# design.net
KiCad netlist of a schematic drawn in Altium Designer
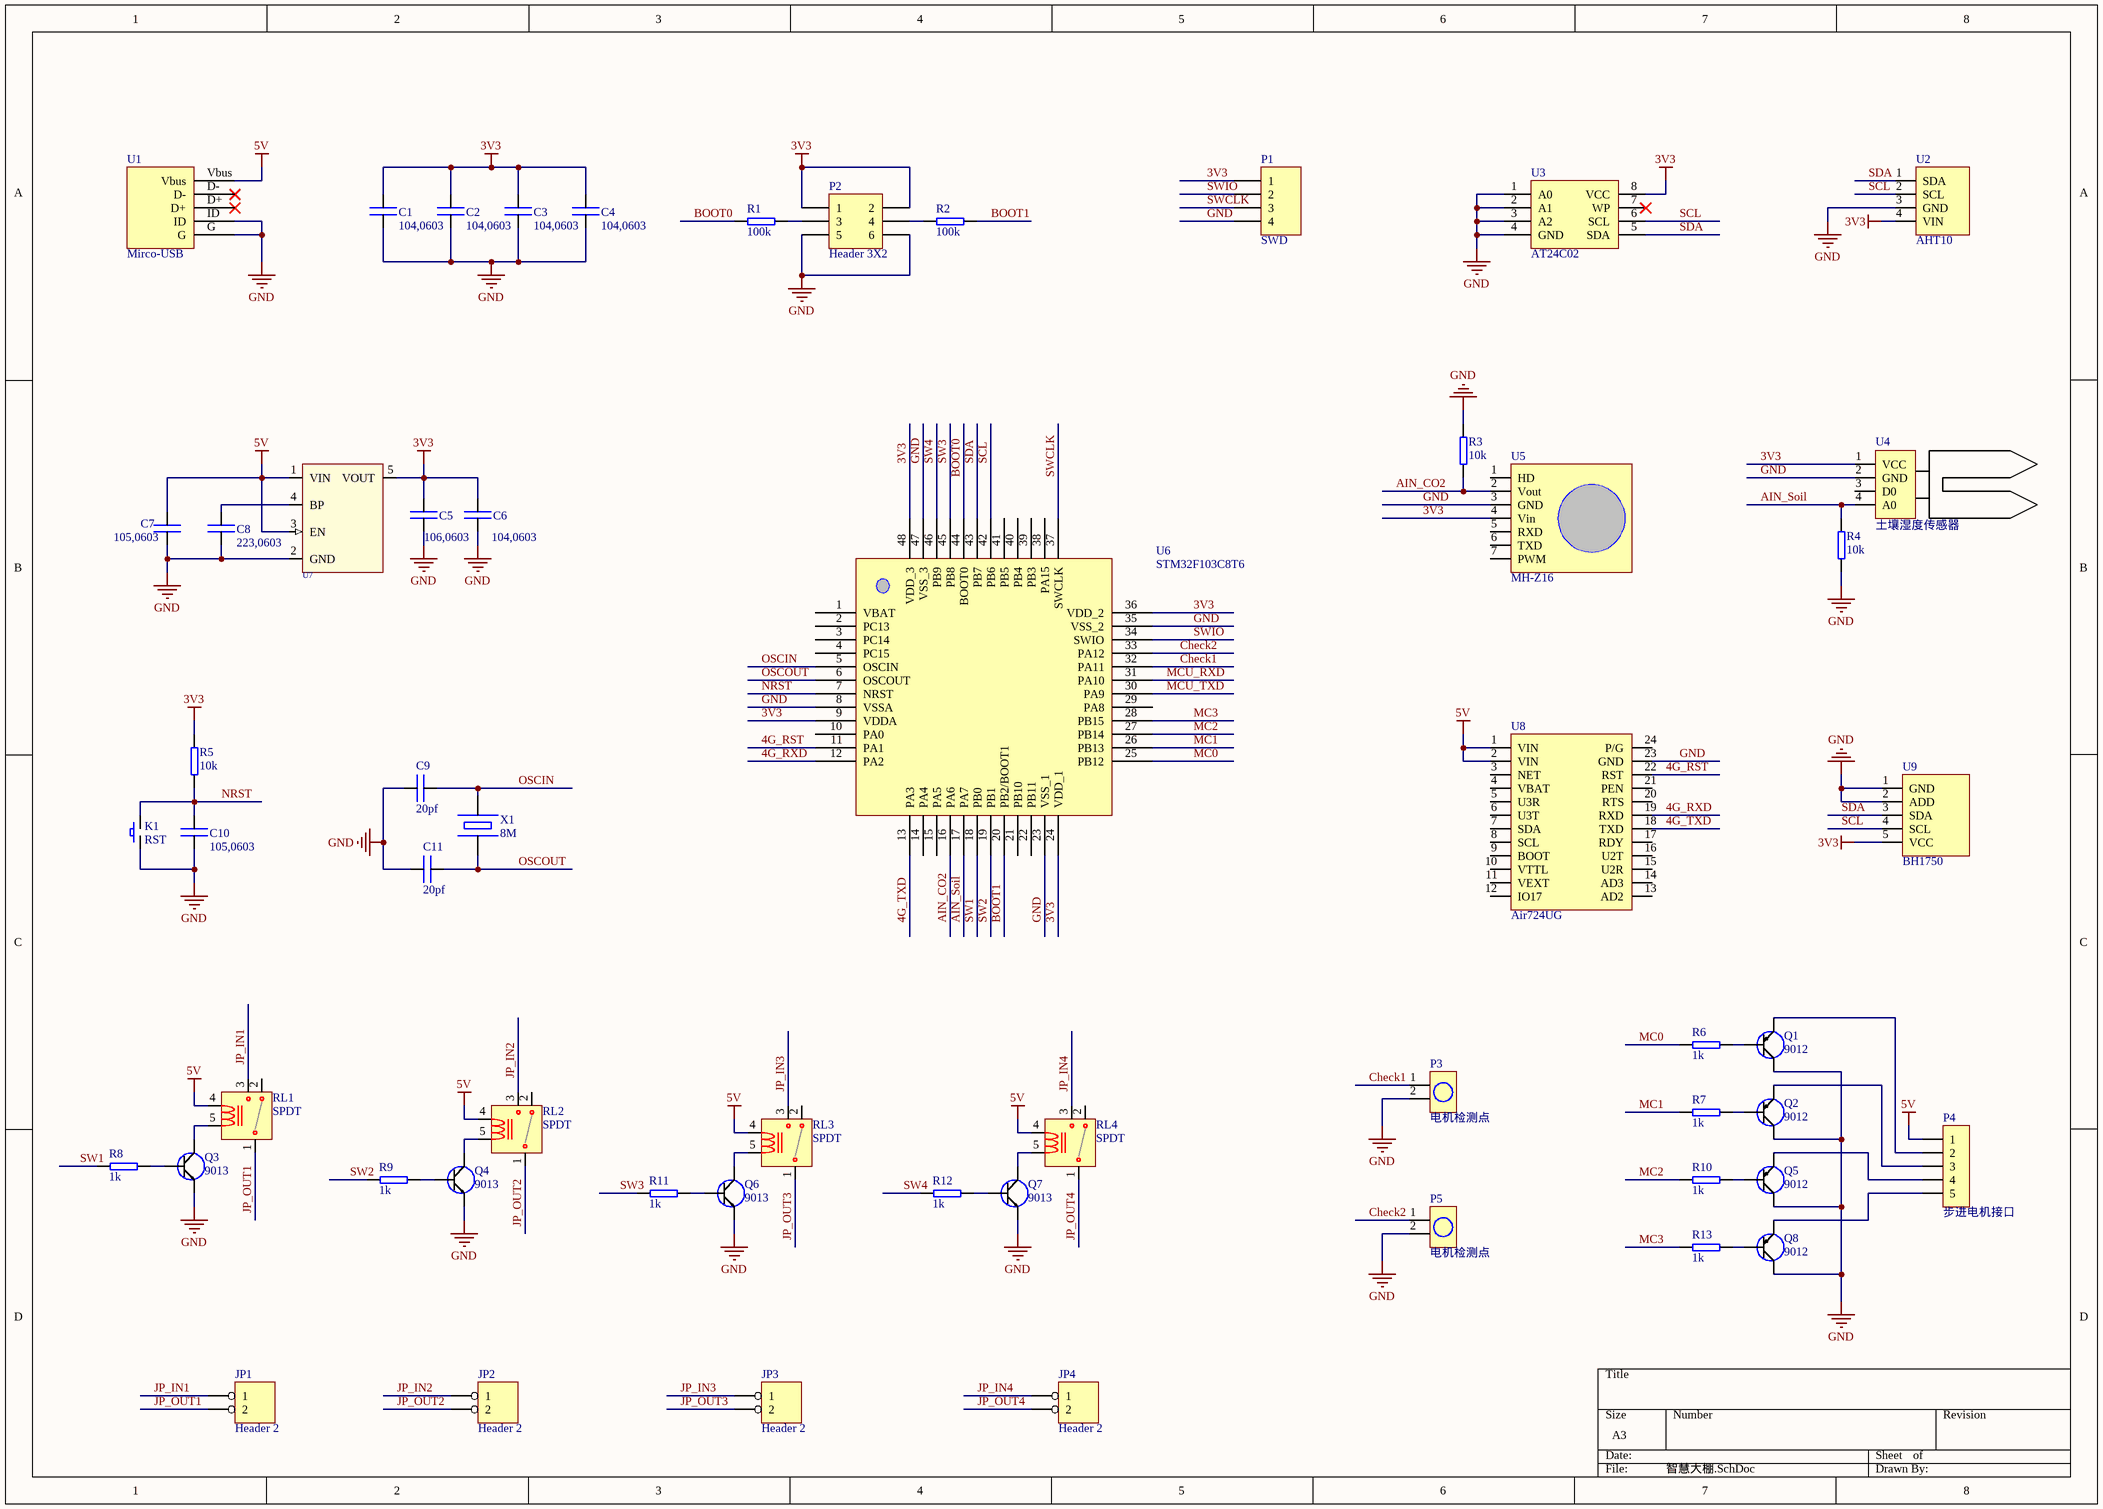
[diagram p0: 智慧大棚.SchDoc]

(export (version "E")
  (design (tool "Eeschema 10.0.6"))
  (components
    (comp (ref "C1")
      (value "104,0603")
      (description "电容")
      (libsource (lib "altium-import") (part "root_0_CAP_"))
    )
    (comp (ref "C2")
      (value "104,0603")
      (description "电容")
      (libsource (lib "altium-import") (part "root_0_CAP_"))
    )
    (comp (ref "C3")
      (value "104,0603")
      (description "电容")
      (libsource (lib "altium-import") (part "root_0_CAP_"))
    )
    (comp (ref "C4")
      (value "104,0603")
      (description "电容")
      (libsource (lib "altium-import") (part "root_0_CAP_"))
    )
    (comp (ref "C5") (value "106,0603") (description "电容") (libsource (lib "智慧大棚") (part "CAP")))
    (comp (ref "C6") (value "104,0603") (description "电容") (libsource (lib "智慧大棚") (part "CAP")))
    (comp (ref "C7")
      (value "105,0603")
      (description "电容")
      (libsource (lib "altium-import") (part "root_0_CAP_"))
    )
    (comp (ref "C8")
      (value "223,0603")
      (description "电容")
      (libsource (lib "altium-import") (part "root_0_CAP_"))
    )
    (comp (ref "C9") (value "20pf") (description "电容") (libsource (lib "altium-import") (part "root_1_CAP_")))
    (comp (ref "C10")
      (value "105,0603")
      (description "电容")
      (libsource (lib "altium-import") (part "root_0_CAP_"))
    )
    (comp (ref "C11")
      (value "20pf")
      (description "电容")
      (libsource (lib "altium-import") (part "root_1_CAP_"))
    )
    (comp (ref "JP1") (value "Header 2") (description "接线端子") (libsource (lib "智慧大棚") (part "Header 2")))
    (comp (ref "JP2") (value "Header 2") (description "接线端子") (libsource (lib "智慧大棚") (part "Header 2")))
    (comp (ref "JP3") (value "Header 2") (description "接线端子") (libsource (lib "智慧大棚") (part "Header 2")))
    (comp (ref "JP4") (value "Header 2") (description "接线端子") (libsource (lib "智慧大棚") (part "Header 2")))
    (comp (ref "K1")
      (value "RST")
      (description "微动开关")
      (libsource (lib "altium-import") (part "root_1_KEY_"))
    )
    (comp (ref "P1")
      (value "SWD")
      (footprint "HDR1X4")
      (description "Header, 4-Pin")
      (fields (field (name "PUBLISHER") "Altium Limited"))
      (libsource (lib "altium-import") (part "root_0_Header 4_"))
    )
    (comp (ref "P2")
      (value "Header 3X2")
      (footprint "HDR2X3")
      (description "Header, 3-Pin, Dual row")
      (fields (field (name "PUBLISHER") "Altium Limited"))
      (libsource (lib "altium-import") (part "root_0_Header 3X2_"))
    )
    (comp (ref "P3")
      (value "电机检测点")
      (description "电机位置检测点")
      (libsource (lib "altium-import") (part "root_0_Header 2IN_"))
    )
    (comp (ref "P4")
      (value "步进电机接口")
      (description "Header, 5-Pin")
      (libsource (lib "智慧大棚") (part "Header 5"))
    )
    (comp (ref "P5")
      (value "电机检测点")
      (description "电机位置检测点")
      (libsource (lib "altium-import") (part "root_0_Header 2IN_"))
    )
    (comp (ref "Q1")
      (value "9012")
      (description "PNP型三极管")
      (libsource (lib "altium-import") (part "root_0_PNP_"))
    )
    (comp (ref "Q2")
      (value "9012")
      (description "PNP型三极管")
      (libsource (lib "altium-import") (part "root_0_PNP_"))
    )
    (comp (ref "Q3") (value "9013") (libsource (lib "altium-import") (part "root_0_9013_")))
    (comp (ref "Q4") (value "9013") (libsource (lib "altium-import") (part "root_0_9013_")))
    (comp (ref "Q5")
      (value "9012")
      (description "PNP型三极管")
      (libsource (lib "altium-import") (part "root_0_PNP_"))
    )
    (comp (ref "Q6") (value "9013") (libsource (lib "altium-import") (part "root_0_9013_")))
    (comp (ref "Q7") (value "9013") (libsource (lib "altium-import") (part "root_0_9013_")))
    (comp (ref "Q8")
      (value "9012")
      (description "PNP型三极管")
      (libsource (lib "altium-import") (part "root_0_PNP_"))
    )
    (comp (ref "R1") (value "100k") (description "电阻") (libsource (lib "智慧大棚") (part "RES")))
    (comp (ref "R2") (value "100k") (description "电阻") (libsource (lib "智慧大棚") (part "RES")))
    (comp (ref "R3") (value "10k") (description "电阻") (libsource (lib "altium-import") (part "root_1_RES_")))
    (comp (ref "R4") (value "10k") (description "电阻") (libsource (lib "altium-import") (part "root_1_RES_")))
    (comp (ref "R5") (value "10k") (description "电阻") (libsource (lib "altium-import") (part "root_1_RES_")))
    (comp (ref "R6") (value "1k") (description "电阻") (libsource (lib "altium-import") (part "root_0_RES_")))
    (comp (ref "R7") (value "1k") (description "电阻") (libsource (lib "altium-import") (part "root_0_RES_")))
    (comp (ref "R8") (value "1k") (description "电阻") (libsource (lib "altium-import") (part "root_0_RES_")))
    (comp (ref "R9") (value "1k") (description "电阻") (libsource (lib "altium-import") (part "root_0_RES_")))
    (comp (ref "R10") (value "1k") (description "电阻") (libsource (lib "altium-import") (part "root_0_RES_")))
    (comp (ref "R11") (value "1k") (description "电阻") (libsource (lib "altium-import") (part "root_0_RES_")))
    (comp (ref "R12") (value "1k") (description "电阻") (libsource (lib "altium-import") (part "root_0_RES_")))
    (comp (ref "R13") (value "1k") (description "电阻") (libsource (lib "altium-import") (part "root_0_RES_")))
    (comp (ref "RL1") (value "SPDT") (libsource (lib "altium-import") (part "root_0_SPDT_")))
    (comp (ref "RL2") (value "SPDT") (libsource (lib "altium-import") (part "root_0_SPDT_")))
    (comp (ref "RL3") (value "SPDT") (libsource (lib "altium-import") (part "root_0_SPDT_")))
    (comp (ref "RL4") (value "SPDT") (libsource (lib "altium-import") (part "root_0_SPDT_")))
    (comp (ref "U1")
      (value "Mirco-USB")
      (footprint "Micro_USB")
      (description "Mirco-USB接口")
      (libsource (lib "altium-import") (part "root_0_Mirco-USB_"))
    )
    (comp (ref "U2")
      (value "AHT10")
      (description "温湿度传感器")
      (libsource (lib "altium-import") (part "root_0_AHT10_"))
    )
    (comp (ref "U3")
      (value "AT24C02")
      (description "EEPROM器件")
      (libsource (lib "altium-import") (part "root_0_AT24C02_"))
    )
    (comp (ref "U4") (value "土壤湿度传感器") (libsource (lib "altium-import") (part "root_0_Soil_")))
    (comp (ref "U5") (value "MH-Z16") (description "二氧化碳传感器") (libsource (lib "智慧大棚") (part "MH-Z16")))
    (comp (ref "U6")
      (value "STM32F103C8T6")
      (footprint "48P")
      (description "MCU 32bit")
      (libsource (lib "altium-import") (part "root_0_STM32F103C8T6_"))
    )
    (comp (ref "U7")
      (value "RT9193")
      (description "稳压")
      (fields (field (name "ICA_PARTNUM") "$$2191094$$RT9193-15CU5") (field (name "PART NUMBER") "TMP-13"))
      (libsource (lib "altium-import") (part "root_0_RT9193X_5P_"))
    )
    (comp (ref "U8")
      (value "Air724UG")
      (description "4G模块")
      (libsource (lib "altium-import") (part "root_0_Air724UG_"))
    )
    (comp (ref "U9")
      (value "BH1750")
      (description "光照传感器")
      (libsource (lib "altium-import") (part "root_0_BH1750_"))
    )
    (comp (ref "X1")
      (value "8M")
      (description "晶振")
      (libsource (lib "altium-import") (part "root_1_CRYSTAL_"))
    )
  )
  (nets
    (net (code "1") (name "/4G_RST") (class "Default")
      (node (ref "U6") (pin "11") (pinfunction "PA1_11") (pintype "passive"))
      (node (ref "U8") (pin "22") (pinfunction "RST_22") (pintype "passive"))
    )
    (net (code "2") (name "/4G_RXD") (class "Default")
      (node (ref "U6") (pin "12") (pinfunction "PA2_12") (pintype "passive"))
      (node (ref "U8") (pin "19") (pinfunction "RXD_19") (pintype "passive"))
    )
    (net (code "3") (name "/4G_TXD") (class "Default")
      (node (ref "U6") (pin "13") (pinfunction "PA3_13") (pintype "passive"))
      (node (ref "U8") (pin "18") (pinfunction "TXD_18") (pintype "passive"))
    )
    (net (code "4") (name "/AIN_CO2") (class "Default")
      (node (ref "R3") (pin "1") (pinfunction "1_1") (pintype "passive"))
      (node (ref "U5") (pin "2") (pinfunction "Vout_2") (pintype "passive"))
      (node (ref "U6") (pin "16") (pinfunction "PA6_16") (pintype "passive"))
    )
    (net (code "5") (name "/AIN_Soil") (class "Default")
      (node (ref "R4") (pin "2") (pinfunction "2_2") (pintype "passive"))
      (node (ref "U4") (pin "4") (pinfunction "A0_4") (pintype "passive"))
      (node (ref "U6") (pin "17") (pinfunction "PA7_17") (pintype "passive"))
    )
    (net (code "6") (name "/BOOT0") (class "Default")
      (node (ref "R1") (pin "1") (pinfunction "1_1") (pintype "passive"))
      (node (ref "U6") (pin "44") (pinfunction "BOOT0_44") (pintype "passive"))
    )
    (net (code "7") (name "/BOOT1") (class "Default")
      (node (ref "R2") (pin "2") (pinfunction "2_2") (pintype "passive"))
      (node (ref "U6") (pin "20") (pinfunction "PB2/BOOT1_20") (pintype "passive"))
    )
    (net (code "8") (name "/Check1") (class "Default")
      (node (ref "P3") (pin "1") (pinfunction "1_1") (pintype "passive"))
      (node (ref "U6") (pin "32") (pinfunction "PA11_32") (pintype "passive"))
    )
    (net (code "9") (name "/Check2") (class "Default")
      (node (ref "P5") (pin "1") (pinfunction "1_1") (pintype "passive"))
      (node (ref "U6") (pin "33") (pinfunction "PA12_33") (pintype "passive"))
    )
    (net (code "10") (name "/JP_IN1") (class "Default")
      (node (ref "JP1") (pin "1") (pinfunction "1_1") (pintype "passive"))
      (node (ref "RL1") (pin "3") (pinfunction "3_3") (pintype "passive"))
    )
    (net (code "11") (name "/JP_IN2") (class "Default")
      (node (ref "JP2") (pin "1") (pinfunction "1_1") (pintype "passive"))
      (node (ref "RL2") (pin "3") (pinfunction "3_3") (pintype "passive"))
    )
    (net (code "12") (name "/JP_IN3") (class "Default")
      (node (ref "JP3") (pin "1") (pinfunction "1_1") (pintype "passive"))
      (node (ref "RL3") (pin "3") (pinfunction "3_3") (pintype "passive"))
    )
    (net (code "13") (name "/JP_IN4") (class "Default")
      (node (ref "JP4") (pin "1") (pinfunction "1_1") (pintype "passive"))
      (node (ref "RL4") (pin "3") (pinfunction "3_3") (pintype "passive"))
    )
    (net (code "14") (name "/JP_OUT1") (class "Default")
      (node (ref "JP1") (pin "2") (pinfunction "2_2") (pintype "passive"))
      (node (ref "RL1") (pin "1") (pinfunction "1_1") (pintype "passive"))
    )
    (net (code "15") (name "/JP_OUT2") (class "Default")
      (node (ref "JP2") (pin "2") (pinfunction "2_2") (pintype "passive"))
      (node (ref "RL2") (pin "1") (pinfunction "1_1") (pintype "passive"))
    )
    (net (code "16") (name "/JP_OUT3") (class "Default")
      (node (ref "JP3") (pin "2") (pinfunction "2_2") (pintype "passive"))
      (node (ref "RL3") (pin "1") (pinfunction "1_1") (pintype "passive"))
    )
    (net (code "17") (name "/JP_OUT4") (class "Default")
      (node (ref "JP4") (pin "2") (pinfunction "2_2") (pintype "passive"))
      (node (ref "RL4") (pin "1") (pinfunction "1_1") (pintype "passive"))
    )
    (net (code "18") (name "/MC0") (class "Default")
      (node (ref "R6") (pin "1") (pinfunction "1_1") (pintype "passive"))
      (node (ref "U6") (pin "25") (pinfunction "PB12_25") (pintype "passive"))
    )
    (net (code "19") (name "/MC1") (class "Default")
      (node (ref "R7") (pin "1") (pinfunction "1_1") (pintype "passive"))
      (node (ref "U6") (pin "26") (pinfunction "PB13_26") (pintype "passive"))
    )
    (net (code "20") (name "/MC2") (class "Default")
      (node (ref "R10") (pin "1") (pinfunction "1_1") (pintype "passive"))
      (node (ref "U6") (pin "27") (pinfunction "PB14_27") (pintype "passive"))
    )
    (net (code "21") (name "/MC3") (class "Default")
      (node (ref "R13") (pin "1") (pinfunction "1_1") (pintype "passive"))
      (node (ref "U6") (pin "28") (pinfunction "PB15_28") (pintype "passive"))
    )
    (net (code "22") (name "/MCU_RXD") (class "Default")
      (node (ref "U6") (pin "31") (pinfunction "PA10_31") (pintype "passive"))
    )
    (net (code "23") (name "/MCU_TXD") (class "Default")
      (node (ref "U6") (pin "30") (pinfunction "PA9_30") (pintype "passive"))
    )
    (net (code "24") (name "/NRST") (class "Default")
      (node (ref "C10") (pin "1") (pinfunction "1_1") (pintype "passive"))
      (node (ref "K1") (pin "2") (pintype "passive"))
      (node (ref "R5") (pin "1") (pinfunction "1_1") (pintype "passive"))
      (node (ref "U6") (pin "7") (pinfunction "NRST_7") (pintype "passive"))
    )
    (net (code "25") (name "/OSCIN") (class "Default")
      (node (ref "C9") (pin "2") (pinfunction "2_2") (pintype "passive"))
      (node (ref "U6") (pin "5") (pinfunction "OSCIN_5") (pintype "passive"))
      (node (ref "X1") (pin "2") (pinfunction "2_2") (pintype "passive"))
    )
    (net (code "26") (name "/OSCOUT") (class "Default")
      (node (ref "C11") (pin "2") (pinfunction "2_2") (pintype "passive"))
      (node (ref "U6") (pin "6") (pinfunction "OSCOUT_6") (pintype "passive"))
      (node (ref "X1") (pin "1") (pinfunction "1_1") (pintype "passive"))
    )
    (net (code "27") (name "/SCL") (class "Default")
      (node (ref "U2") (pin "2") (pinfunction "SCL_2") (pintype "passive"))
      (node (ref "U3") (pin "6") (pinfunction "SCL_6") (pintype "passive"))
      (node (ref "U6") (pin "42") (pinfunction "PB6_42") (pintype "passive"))
      (node (ref "U9") (pin "4") (pinfunction "SCL_4") (pintype "passive"))
    )
    (net (code "28") (name "/SDA") (class "Default")
      (node (ref "U2") (pin "1") (pinfunction "SDA_1") (pintype "passive"))
      (node (ref "U3") (pin "5") (pinfunction "SDA_5") (pintype "passive"))
      (node (ref "U6") (pin "43") (pinfunction "PB7_43") (pintype "passive"))
      (node (ref "U9") (pin "3") (pinfunction "SDA_3") (pintype "passive"))
    )
    (net (code "29") (name "/SW1") (class "Default")
      (node (ref "R8") (pin "1") (pinfunction "1_1") (pintype "passive"))
      (node (ref "U6") (pin "18") (pinfunction "PB0_18") (pintype "passive"))
    )
    (net (code "30") (name "/SW2") (class "Default")
      (node (ref "R9") (pin "1") (pinfunction "1_1") (pintype "passive"))
      (node (ref "U6") (pin "19") (pinfunction "PB1_19") (pintype "passive"))
    )
    (net (code "31") (name "/SW3") (class "Default")
      (node (ref "R11") (pin "1") (pinfunction "1_1") (pintype "passive"))
      (node (ref "U6") (pin "45") (pinfunction "PB8_45") (pintype "passive"))
    )
    (net (code "32") (name "/SW4") (class "Default")
      (node (ref "R12") (pin "1") (pinfunction "1_1") (pintype "passive"))
      (node (ref "U6") (pin "46") (pinfunction "PB9_46") (pintype "passive"))
    )
    (net (code "33") (name "/SWCLK") (class "Default")
      (node (ref "P1") (pin "3") (pinfunction "3_3") (pintype "passive"))
      (node (ref "U6") (pin "37") (pinfunction "SWCLK_37") (pintype "passive"))
    )
    (net (code "34") (name "/SWIO") (class "Default")
      (node (ref "P1") (pin "2") (pinfunction "2_2") (pintype "passive"))
      (node (ref "U6") (pin "34") (pinfunction "SWIO_34") (pintype "passive"))
    )
    (net (code "35") (name "3V3") (class "Default")
      (node (ref "C1") (pin "1") (pinfunction "1_1") (pintype "passive"))
      (node (ref "C2") (pin "1") (pinfunction "1_1") (pintype "passive"))
      (node (ref "C3") (pin "1") (pinfunction "1_1") (pintype "passive"))
      (node (ref "C4") (pin "1") (pinfunction "1_1") (pintype "passive"))
      (node (ref "C5") (pin "1") (pinfunction "1_1") (pintype "passive"))
      (node (ref "C6") (pin "1") (pinfunction "1_1") (pintype "passive"))
      (node (ref "P1") (pin "1") (pinfunction "1_1") (pintype "passive"))
      (node (ref "P2") (pin "1") (pinfunction "1_1") (pintype "passive"))
      (node (ref "P2") (pin "2") (pinfunction "2_2") (pintype "passive"))
      (node (ref "R5") (pin "2") (pinfunction "2_2") (pintype "passive"))
      (node (ref "U2") (pin "4") (pinfunction "VIN_4") (pintype "passive"))
      (node (ref "U3") (pin "8") (pinfunction "VCC_8") (pintype "passive"))
      (node (ref "U4") (pin "1") (pinfunction "VCC_1") (pintype "passive"))
      (node (ref "U5") (pin "4") (pinfunction "Vin_4") (pintype "passive"))
      (node (ref "U6") (pin "24") (pinfunction "VDD_1_24") (pintype "passive"))
      (node (ref "U6") (pin "36") (pinfunction "VDD_2_36") (pintype "passive"))
      (node (ref "U6") (pin "48") (pinfunction "VDD_3_48") (pintype "passive"))
      (node (ref "U6") (pin "9") (pinfunction "VDDA_9") (pintype "passive"))
      (node (ref "U7") (pin "5") (pinfunction "VOUT_5") (pintype "power_in"))
      (node (ref "U9") (pin "5") (pinfunction "VCC_5") (pintype "passive"))
    )
    (net (code "36") (name "5V") (class "Default")
      (node (ref "C7") (pin "1") (pinfunction "1_1") (pintype "passive"))
      (node (ref "P4") (pin "1") (pinfunction "1_1") (pintype "passive"))
      (node (ref "RL1") (pin "4") (pinfunction "4_4") (pintype "passive"))
      (node (ref "RL2") (pin "4") (pinfunction "4_4") (pintype "passive"))
      (node (ref "RL3") (pin "4") (pinfunction "4_4") (pintype "passive"))
      (node (ref "RL4") (pin "4") (pinfunction "4_4") (pintype "passive"))
      (node (ref "U1") (pin "Vbus") (pinfunction "Vbus_Vbus") (pintype "passive"))
      (node (ref "U7") (pin "1") (pinfunction "VIN_1") (pintype "power_in"))
      (node (ref "U7") (pin "3") (pinfunction "EN_3") (pintype "input"))
      (node (ref "U8") (pin "1") (pinfunction "VIN_1") (pintype "passive"))
      (node (ref "U8") (pin "2") (pinfunction "VIN_2") (pintype "passive"))
    )
    (net (code "37") (name "GND") (class "Default")
      (node (ref "C1") (pin "2") (pinfunction "2_2") (pintype "passive"))
      (node (ref "C10") (pin "2") (pinfunction "2_2") (pintype "passive"))
      (node (ref "C11") (pin "1") (pinfunction "1_1") (pintype "passive"))
      (node (ref "C2") (pin "2") (pinfunction "2_2") (pintype "passive"))
      (node (ref "C3") (pin "2") (pinfunction "2_2") (pintype "passive"))
      (node (ref "C4") (pin "2") (pinfunction "2_2") (pintype "passive"))
      (node (ref "C5") (pin "2") (pinfunction "2_2") (pintype "passive"))
      (node (ref "C6") (pin "2") (pinfunction "2_2") (pintype "passive"))
      (node (ref "C7") (pin "2") (pinfunction "2_2") (pintype "passive"))
      (node (ref "C8") (pin "2") (pinfunction "2_2") (pintype "passive"))
      (node (ref "C9") (pin "1") (pinfunction "1_1") (pintype "passive"))
      (node (ref "K1") (pin "1") (pintype "passive"))
      (node (ref "P1") (pin "4") (pinfunction "4_4") (pintype "passive"))
      (node (ref "P2") (pin "5") (pinfunction "5_5") (pintype "passive"))
      (node (ref "P2") (pin "6") (pinfunction "6_6") (pintype "passive"))
      (node (ref "P3") (pin "2") (pinfunction "2_2") (pintype "passive"))
      (node (ref "P5") (pin "2") (pinfunction "2_2") (pintype "passive"))
      (node (ref "Q1") (pin "2") (pinfunction "2_2") (pintype "passive"))
      (node (ref "Q2") (pin "2") (pinfunction "2_2") (pintype "passive"))
      (node (ref "Q3") (pin "2") (pinfunction "2_2") (pintype "passive"))
      (node (ref "Q4") (pin "2") (pinfunction "2_2") (pintype "passive"))
      (node (ref "Q5") (pin "2") (pinfunction "2_2") (pintype "passive"))
      (node (ref "Q6") (pin "2") (pinfunction "2_2") (pintype "passive"))
      (node (ref "Q7") (pin "2") (pinfunction "2_2") (pintype "passive"))
      (node (ref "Q8") (pin "2") (pinfunction "2_2") (pintype "passive"))
      (node (ref "R3") (pin "2") (pinfunction "2_2") (pintype "passive"))
      (node (ref "R4") (pin "1") (pinfunction "1_1") (pintype "passive"))
      (node (ref "U1") (pin "G") (pinfunction "G_G") (pintype "passive"))
      (node (ref "U1") (pin "ID") (pinfunction "ID_ID") (pintype "passive"))
      (node (ref "U2") (pin "3") (pinfunction "GND_3") (pintype "passive"))
      (node (ref "U3") (pin "1") (pinfunction "A0_1") (pintype "passive"))
      (node (ref "U3") (pin "2") (pinfunction "A1_2") (pintype "passive"))
      (node (ref "U3") (pin "3") (pinfunction "A2_3") (pintype "passive"))
      (node (ref "U3") (pin "4") (pinfunction "GND_4") (pintype "passive"))
      (node (ref "U4") (pin "2") (pinfunction "GND_2") (pintype "passive"))
      (node (ref "U5") (pin "3") (pinfunction "GND_3") (pintype "passive"))
      (node (ref "U6") (pin "23") (pinfunction "VSS_1_23") (pintype "passive"))
      (node (ref "U6") (pin "35") (pinfunction "VSS_2_35") (pintype "passive"))
      (node (ref "U6") (pin "47") (pinfunction "VSS_3_47") (pintype "passive"))
      (node (ref "U6") (pin "8") (pinfunction "VSSA_8") (pintype "passive"))
      (node (ref "U7") (pin "2") (pinfunction "GND_2") (pintype "power_in"))
      (node (ref "U8") (pin "23") (pinfunction "GND_23") (pintype "passive"))
      (node (ref "U9") (pin "1") (pinfunction "GND_1") (pintype "passive"))
      (node (ref "U9") (pin "2") (pinfunction "ADD_2") (pintype "passive"))
    )
    (net (code "38") (name "Net-(P2-Pad3)") (class "Default")
      (node (ref "P2") (pin "3") (pinfunction "3_3") (pintype "passive"))
      (node (ref "R1") (pin "2") (pinfunction "2_2") (pintype "passive"))
    )
    (net (code "39") (name "Net-(P2-Pad4)") (class "Default")
      (node (ref "P2") (pin "4") (pinfunction "4_4") (pintype "passive"))
      (node (ref "R2") (pin "1") (pinfunction "1_1") (pintype "passive"))
    )
    (net (code "40") (name "Net-(P4-Pad2)") (class "Default")
      (node (ref "P4") (pin "2") (pinfunction "2_2") (pintype "passive"))
      (node (ref "Q1") (pin "3") (pinfunction "3_3") (pintype "passive"))
    )
    (net (code "41") (name "Net-(P4-Pad3)") (class "Default")
      (node (ref "P4") (pin "3") (pinfunction "3_3") (pintype "passive"))
      (node (ref "Q2") (pin "3") (pinfunction "3_3") (pintype "passive"))
    )
    (net (code "42") (name "Net-(P4-Pad4)") (class "Default")
      (node (ref "P4") (pin "4") (pinfunction "4_4") (pintype "passive"))
      (node (ref "Q5") (pin "3") (pinfunction "3_3") (pintype "passive"))
    )
    (net (code "43") (name "Net-(P4-Pad5)") (class "Default")
      (node (ref "P4") (pin "5") (pinfunction "5_5") (pintype "passive"))
      (node (ref "Q8") (pin "3") (pinfunction "3_3") (pintype "passive"))
    )
    (net (code "44") (name "Net-(Q1-Pad1)") (class "Default")
      (node (ref "Q1") (pin "1") (pinfunction "1_1") (pintype "passive"))
      (node (ref "R6") (pin "2") (pinfunction "2_2") (pintype "passive"))
    )
    (net (code "45") (name "Net-(Q2-Pad1)") (class "Default")
      (node (ref "Q2") (pin "1") (pinfunction "1_1") (pintype "passive"))
      (node (ref "R7") (pin "2") (pinfunction "2_2") (pintype "passive"))
    )
    (net (code "46") (name "Net-(Q3-Pad1)") (class "Default")
      (node (ref "Q3") (pin "1") (pinfunction "1_1") (pintype "passive"))
      (node (ref "R8") (pin "2") (pinfunction "2_2") (pintype "passive"))
    )
    (net (code "47") (name "Net-(Q3-Pad3)") (class "Default")
      (node (ref "Q3") (pin "3") (pinfunction "3_3") (pintype "passive"))
      (node (ref "RL1") (pin "5") (pinfunction "5_5") (pintype "passive"))
    )
    (net (code "48") (name "Net-(Q4-Pad1)") (class "Default")
      (node (ref "Q4") (pin "1") (pinfunction "1_1") (pintype "passive"))
      (node (ref "R9") (pin "2") (pinfunction "2_2") (pintype "passive"))
    )
    (net (code "49") (name "Net-(Q4-Pad3)") (class "Default")
      (node (ref "Q4") (pin "3") (pinfunction "3_3") (pintype "passive"))
      (node (ref "RL2") (pin "5") (pinfunction "5_5") (pintype "passive"))
    )
    (net (code "50") (name "Net-(Q5-Pad1)") (class "Default")
      (node (ref "Q5") (pin "1") (pinfunction "1_1") (pintype "passive"))
      (node (ref "R10") (pin "2") (pinfunction "2_2") (pintype "passive"))
    )
    (net (code "51") (name "Net-(Q6-Pad1)") (class "Default")
      (node (ref "Q6") (pin "1") (pinfunction "1_1") (pintype "passive"))
      (node (ref "R11") (pin "2") (pinfunction "2_2") (pintype "passive"))
    )
    (net (code "52") (name "Net-(Q6-Pad3)") (class "Default")
      (node (ref "Q6") (pin "3") (pinfunction "3_3") (pintype "passive"))
      (node (ref "RL3") (pin "5") (pinfunction "5_5") (pintype "passive"))
    )
    (net (code "53") (name "Net-(Q7-Pad1)") (class "Default")
      (node (ref "Q7") (pin "1") (pinfunction "1_1") (pintype "passive"))
      (node (ref "R12") (pin "2") (pinfunction "2_2") (pintype "passive"))
    )
    (net (code "54") (name "Net-(Q7-Pad3)") (class "Default")
      (node (ref "Q7") (pin "3") (pinfunction "3_3") (pintype "passive"))
      (node (ref "RL4") (pin "5") (pinfunction "5_5") (pintype "passive"))
    )
    (net (code "55") (name "Net-(Q8-Pad1)") (class "Default")
      (node (ref "Q8") (pin "1") (pinfunction "1_1") (pintype "passive"))
      (node (ref "R13") (pin "2") (pinfunction "2_2") (pintype "passive"))
    )
    (net (code "56") (name "Net-(U7-BP)") (class "Default")
      (node (ref "C8") (pin "1") (pinfunction "1_1") (pintype "passive"))
      (node (ref "U7") (pin "4") (pinfunction "BP_4") (pintype "passive"))
    )
    (net (code "57") (name "unconnected-(RL1-Pad2)") (class "Default")
      (node (ref "RL1") (pin "2") (pinfunction "2_2") (pintype "passive"))
    )
    (net (code "58") (name "unconnected-(RL2-Pad2)") (class "Default")
      (node (ref "RL2") (pin "2") (pinfunction "2_2") (pintype "passive"))
    )
    (net (code "59") (name "unconnected-(RL3-Pad2)") (class "Default")
      (node (ref "RL3") (pin "2") (pinfunction "2_2") (pintype "passive"))
    )
    (net (code "60") (name "unconnected-(RL4-Pad2)") (class "Default")
      (node (ref "RL4") (pin "2") (pinfunction "2_2") (pintype "passive"))
    )
    (net (code "61") (name "unconnected-(U1-PadD+)") (class "Default")
      (node (ref "U1") (pin "D+") (pinfunction "D+_D+") (pintype "passive+no_connect"))
    )
    (net (code "62") (name "unconnected-(U1-PadD-)") (class "Default")
      (node (ref "U1") (pin "D-") (pinfunction "D-_D-") (pintype "passive+no_connect"))
    )
    (net (code "63") (name "unconnected-(U3-WP-Pad7)") (class "Default")
      (node (ref "U3") (pin "7") (pinfunction "WP_7") (pintype "passive+no_connect"))
    )
    (net (code "64") (name "unconnected-(U4-D0-Pad3)") (class "Default")
      (node (ref "U4") (pin "3") (pinfunction "D0_3") (pintype "passive"))
    )
    (net (code "65") (name "unconnected-(U5-HD-Pad1)") (class "Default")
      (node (ref "U5") (pin "1") (pinfunction "HD_1") (pintype "passive"))
    )
    (net (code "66") (name "unconnected-(U5-PWM-Pad7)") (class "Default")
      (node (ref "U5") (pin "7") (pinfunction "PWM_7") (pintype "passive"))
    )
    (net (code "67") (name "unconnected-(U5-RXD-Pad5)") (class "Default")
      (node (ref "U5") (pin "5") (pinfunction "RXD_5") (pintype "passive"))
    )
    (net (code "68") (name "unconnected-(U5-TXD-Pad6)") (class "Default")
      (node (ref "U5") (pin "6") (pinfunction "TXD_6") (pintype "passive"))
    )
    (net (code "69") (name "unconnected-(U6-PA0-Pad10)") (class "Default")
      (node (ref "U6") (pin "10") (pinfunction "PA0_10") (pintype "passive"))
    )
    (net (code "70") (name "unconnected-(U6-PA4-Pad14)") (class "Default")
      (node (ref "U6") (pin "14") (pinfunction "PA4_14") (pintype "passive"))
    )
    (net (code "71") (name "unconnected-(U6-PA5-Pad15)") (class "Default")
      (node (ref "U6") (pin "15") (pinfunction "PA5_15") (pintype "passive"))
    )
    (net (code "72") (name "unconnected-(U6-PA8-Pad29)") (class "Default")
      (node (ref "U6") (pin "29") (pinfunction "PA8_29") (pintype "passive"))
    )
    (net (code "73") (name "unconnected-(U6-PA15-Pad38)") (class "Default")
      (node (ref "U6") (pin "38") (pinfunction "PA15_38") (pintype "passive"))
    )
    (net (code "74") (name "unconnected-(U6-PB3-Pad39)") (class "Default")
      (node (ref "U6") (pin "39") (pinfunction "PB3_39") (pintype "passive"))
    )
    (net (code "75") (name "unconnected-(U6-PB4-Pad40)") (class "Default")
      (node (ref "U6") (pin "40") (pinfunction "PB4_40") (pintype "passive"))
    )
    (net (code "76") (name "unconnected-(U6-PB5-Pad41)") (class "Default")
      (node (ref "U6") (pin "41") (pinfunction "PB5_41") (pintype "passive"))
    )
    (net (code "77") (name "unconnected-(U6-PB10-Pad21)") (class "Default")
      (node (ref "U6") (pin "21") (pinfunction "PB10_21") (pintype "passive"))
    )
    (net (code "78") (name "unconnected-(U6-PB11-Pad22)") (class "Default")
      (node (ref "U6") (pin "22") (pinfunction "PB11_22") (pintype "passive"))
    )
    (net (code "79") (name "unconnected-(U6-PC13-Pad2)") (class "Default")
      (node (ref "U6") (pin "2") (pinfunction "PC13_2") (pintype "passive"))
    )
    (net (code "80") (name "unconnected-(U6-PC14-Pad3)") (class "Default")
      (node (ref "U6") (pin "3") (pinfunction "PC14_3") (pintype "passive"))
    )
    (net (code "81") (name "unconnected-(U6-PC15-Pad4)") (class "Default")
      (node (ref "U6") (pin "4") (pinfunction "PC15_4") (pintype "passive"))
    )
    (net (code "82") (name "unconnected-(U6-VBAT-Pad1)") (class "Default")
      (node (ref "U6") (pin "1") (pinfunction "VBAT_1") (pintype "passive"))
    )
    (net (code "83") (name "unconnected-(U8-AD2-Pad13)") (class "Default")
      (node (ref "U8") (pin "13") (pinfunction "AD2_13") (pintype "passive"))
    )
    (net (code "84") (name "unconnected-(U8-AD3-Pad14)") (class "Default")
      (node (ref "U8") (pin "14") (pinfunction "AD3_14") (pintype "passive"))
    )
    (net (code "85") (name "unconnected-(U8-BOOT-Pad9)") (class "Default")
      (node (ref "U8") (pin "9") (pinfunction "BOOT_9") (pintype "passive"))
    )
    (net (code "86") (name "unconnected-(U8-IO17-Pad12)") (class "Default")
      (node (ref "U8") (pin "12") (pinfunction "IO17_12") (pintype "passive"))
    )
    (net (code "87") (name "unconnected-(U8-NET-Pad3)") (class "Default")
      (node (ref "U8") (pin "3") (pinfunction "NET_3") (pintype "passive"))
    )
    (net (code "88") (name "unconnected-(U8-PEN-Pad21)") (class "Default")
      (node (ref "U8") (pin "21") (pinfunction "PEN_21") (pintype "passive"))
    )
    (net (code "89") (name "unconnected-(U8-P{slash}G-Pad24)") (class "Default")
      (node (ref "U8") (pin "24") (pinfunction "P/G_24") (pintype "passive"))
    )
    (net (code "90") (name "unconnected-(U8-RDY-Pad17)") (class "Default")
      (node (ref "U8") (pin "17") (pinfunction "RDY_17") (pintype "passive"))
    )
    (net (code "91") (name "unconnected-(U8-RTS-Pad20)") (class "Default")
      (node (ref "U8") (pin "20") (pinfunction "RTS_20") (pintype "passive"))
    )
    (net (code "92") (name "unconnected-(U8-SCL-Pad8)") (class "Default")
      (node (ref "U8") (pin "8") (pinfunction "SCL_8") (pintype "passive"))
    )
    (net (code "93") (name "unconnected-(U8-SDA-Pad7)") (class "Default")
      (node (ref "U8") (pin "7") (pinfunction "SDA_7") (pintype "passive"))
    )
    (net (code "94") (name "unconnected-(U8-U2R-Pad15)") (class "Default")
      (node (ref "U8") (pin "15") (pinfunction "U2R_15") (pintype "passive"))
    )
    (net (code "95") (name "unconnected-(U8-U2T-Pad16)") (class "Default")
      (node (ref "U8") (pin "16") (pinfunction "U2T_16") (pintype "passive"))
    )
    (net (code "96") (name "unconnected-(U8-U3R-Pad5)") (class "Default")
      (node (ref "U8") (pin "5") (pinfunction "U3R_5") (pintype "passive"))
    )
    (net (code "97") (name "unconnected-(U8-U3T-Pad6)") (class "Default")
      (node (ref "U8") (pin "6") (pinfunction "U3T_6") (pintype "passive"))
    )
    (net (code "98") (name "unconnected-(U8-VBAT-Pad4)") (class "Default")
      (node (ref "U8") (pin "4") (pinfunction "VBAT_4") (pintype "passive"))
    )
    (net (code "99") (name "unconnected-(U8-VEXT-Pad11)") (class "Default")
      (node (ref "U8") (pin "11") (pinfunction "VEXT_11") (pintype "passive"))
    )
    (net (code "100") (name "unconnected-(U8-VTTL-Pad10)") (class "Default")
      (node (ref "U8") (pin "10") (pinfunction "VTTL_10") (pintype "passive"))
    )
  )
)
